# FPGA_Data.net
KiCad netlist of a schematic drawn in Altium Designer
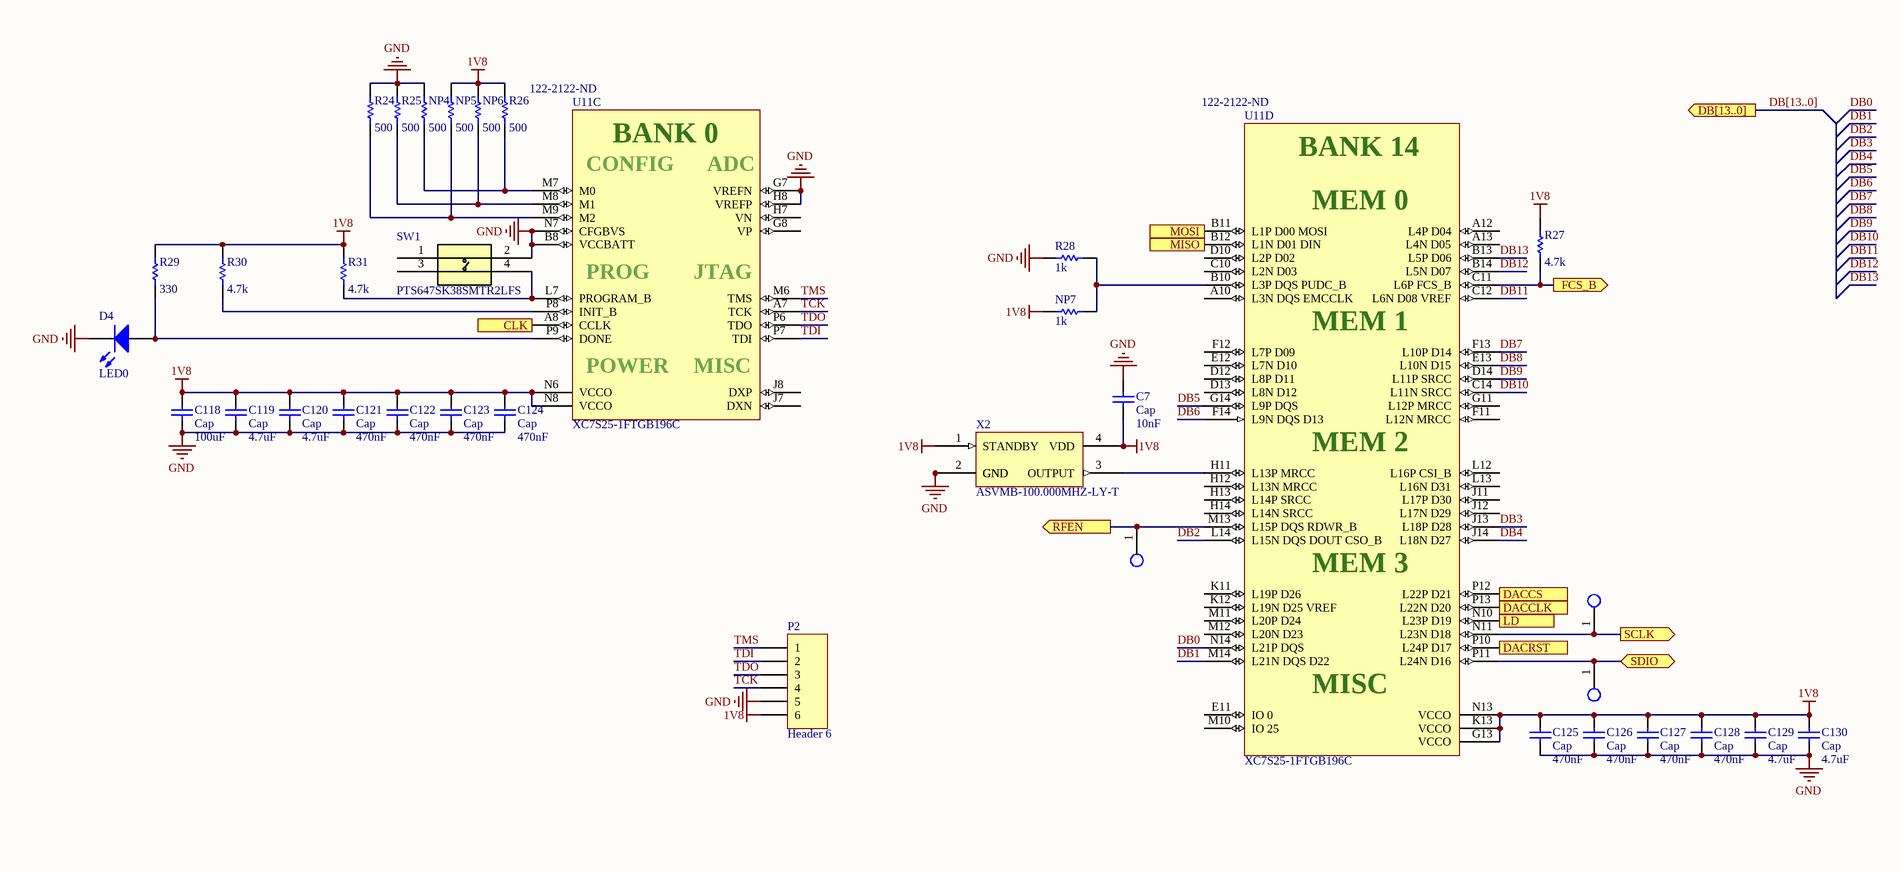
[diagram p0: FPGA Data.SchDoc, left]
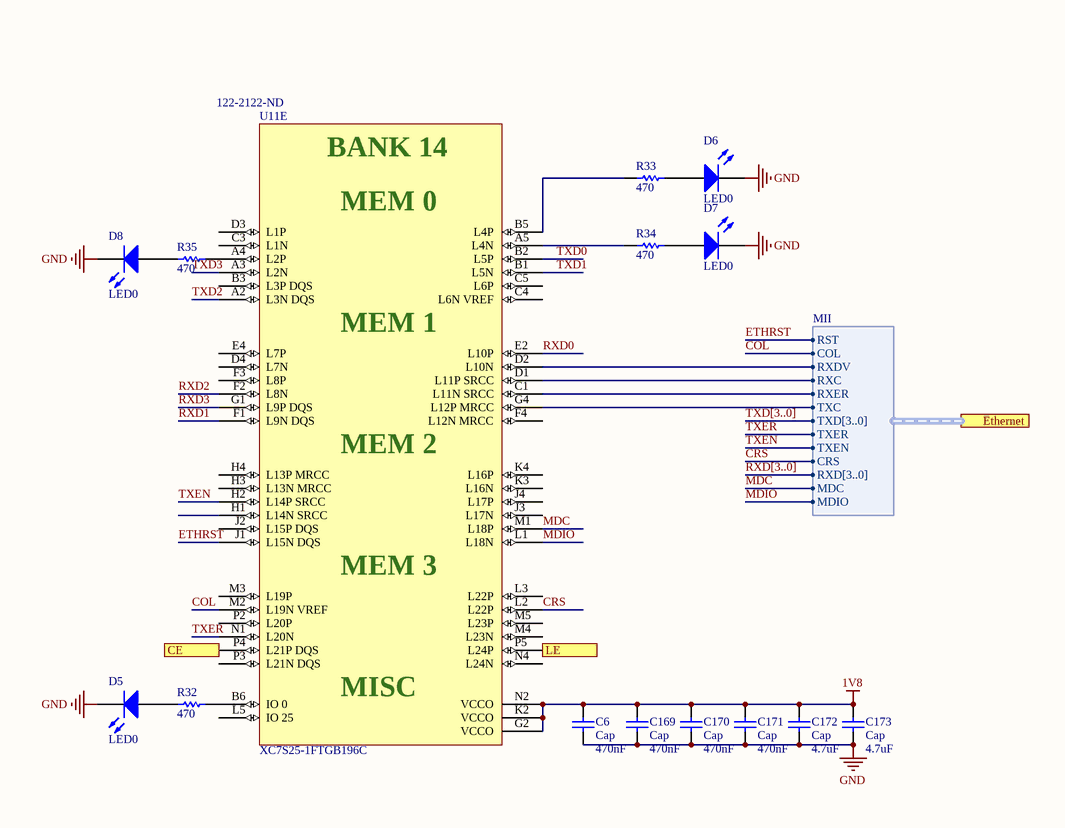
[diagram p1: FPGA Data.SchDoc, right]

(export (version "E")
  (design (tool "Eeschema 10.0.6"))
  (components
    (comp (ref "C6")
      (value "Cap")
      (footprint "1608[0603]")
      (description "Capacitor")
      (fields (field (name "ALTIUM_VALUE") "470nF") (field (name "PUBLISHER") "Altium Limited"))
      (libsource (lib "Miscellaneous Devices") (part "Cap"))
    )
    (comp (ref "C7")
      (value "Cap")
      (footprint "0402-A")
      (description "Capacitor")
      (fields (field (name "ALTIUM_VALUE") "10nF") (field (name "PUBLISHER") "Altium Limited"))
      (libsource (lib "Miscellaneous Devices") (part "Cap"))
    )
    (comp (ref "C118")
      (value "Cap")
      (footprint "C1210")
      (description "Capacitor")
      (fields (field (name "ALTIUM_VALUE") "100uF") (field (name "PUBLISHER") "Altium Limited"))
      (libsource (lib "Miscellaneous Devices") (part "Cap"))
    )
    (comp (ref "C119")
      (value "Cap")
      (footprint "6-0805_M")
      (description "Capacitor")
      (fields (field (name "ALTIUM_VALUE") "4.7uF") (field (name "PUBLISHER") "Altium Limited"))
      (libsource (lib "Miscellaneous Devices") (part "Cap"))
    )
    (comp (ref "C120")
      (value "Cap")
      (footprint "6-0805_M")
      (description "Capacitor")
      (fields (field (name "ALTIUM_VALUE") "4.7uF") (field (name "PUBLISHER") "Altium Limited"))
      (libsource (lib "Miscellaneous Devices") (part "Cap"))
    )
    (comp (ref "C121")
      (value "Cap")
      (footprint "1608[0603]")
      (description "Capacitor")
      (fields (field (name "ALTIUM_VALUE") "470nF") (field (name "PUBLISHER") "Altium Limited"))
      (libsource (lib "Miscellaneous Devices") (part "Cap"))
    )
    (comp (ref "C122")
      (value "Cap")
      (footprint "1608[0603]")
      (description "Capacitor")
      (fields (field (name "ALTIUM_VALUE") "470nF") (field (name "PUBLISHER") "Altium Limited"))
      (libsource (lib "Miscellaneous Devices") (part "Cap"))
    )
    (comp (ref "C123")
      (value "Cap")
      (footprint "1608[0603]")
      (description "Capacitor")
      (fields (field (name "ALTIUM_VALUE") "470nF") (field (name "PUBLISHER") "Altium Limited"))
      (libsource (lib "Miscellaneous Devices") (part "Cap"))
    )
    (comp (ref "C124")
      (value "Cap")
      (footprint "1608[0603]")
      (description "Capacitor")
      (fields (field (name "ALTIUM_VALUE") "470nF") (field (name "PUBLISHER") "Altium Limited"))
      (libsource (lib "Miscellaneous Devices") (part "Cap"))
    )
    (comp (ref "C125")
      (value "Cap")
      (footprint "1608[0603]")
      (description "Capacitor")
      (fields (field (name "ALTIUM_VALUE") "470nF") (field (name "PUBLISHER") "Altium Limited"))
      (libsource (lib "Miscellaneous Devices") (part "Cap"))
    )
    (comp (ref "C126")
      (value "Cap")
      (footprint "1608[0603]")
      (description "Capacitor")
      (fields (field (name "ALTIUM_VALUE") "470nF") (field (name "PUBLISHER") "Altium Limited"))
      (libsource (lib "Miscellaneous Devices") (part "Cap"))
    )
    (comp (ref "C127")
      (value "Cap")
      (footprint "1608[0603]")
      (description "Capacitor")
      (fields (field (name "ALTIUM_VALUE") "470nF") (field (name "PUBLISHER") "Altium Limited"))
      (libsource (lib "Miscellaneous Devices") (part "Cap"))
    )
    (comp (ref "C128")
      (value "Cap")
      (footprint "1608[0603]")
      (description "Capacitor")
      (fields (field (name "ALTIUM_VALUE") "470nF") (field (name "PUBLISHER") "Altium Limited"))
      (libsource (lib "Miscellaneous Devices") (part "Cap"))
    )
    (comp (ref "C129")
      (value "Cap")
      (footprint "6-0805_M")
      (description "Capacitor")
      (fields (field (name "ALTIUM_VALUE") "4.7uF") (field (name "PUBLISHER") "Altium Limited"))
      (libsource (lib "Miscellaneous Devices") (part "Cap"))
    )
    (comp (ref "C130")
      (value "Cap")
      (footprint "6-0805_M")
      (description "Capacitor")
      (fields (field (name "ALTIUM_VALUE") "4.7uF") (field (name "PUBLISHER") "Altium Limited"))
      (libsource (lib "Miscellaneous Devices") (part "Cap"))
    )
    (comp (ref "C169")
      (value "Cap")
      (footprint "1608[0603]")
      (description "Capacitor")
      (fields (field (name "ALTIUM_VALUE") "470nF") (field (name "PUBLISHER") "Altium Limited"))
      (libsource (lib "Miscellaneous Devices") (part "Cap"))
    )
    (comp (ref "C170")
      (value "Cap")
      (footprint "1608[0603]")
      (description "Capacitor")
      (fields (field (name "ALTIUM_VALUE") "470nF") (field (name "PUBLISHER") "Altium Limited"))
      (libsource (lib "Miscellaneous Devices") (part "Cap"))
    )
    (comp (ref "C171")
      (value "Cap")
      (footprint "1608[0603]")
      (description "Capacitor")
      (fields (field (name "ALTIUM_VALUE") "470nF") (field (name "PUBLISHER") "Altium Limited"))
      (libsource (lib "Miscellaneous Devices") (part "Cap"))
    )
    (comp (ref "C172")
      (value "Cap")
      (footprint "6-0805_M")
      (description "Capacitor")
      (fields (field (name "ALTIUM_VALUE") "4.7uF") (field (name "PUBLISHER") "Altium Limited"))
      (libsource (lib "Miscellaneous Devices") (part "Cap"))
    )
    (comp (ref "C173")
      (value "Cap")
      (footprint "6-0805_M")
      (description "Capacitor")
      (fields (field (name "ALTIUM_VALUE") "4.7uF") (field (name "PUBLISHER") "Altium Limited"))
      (libsource (lib "Miscellaneous Devices") (part "Cap"))
    )
    (comp (ref "CLK1")
      (value "5029")
      (footprint "EXPOSED PAD 0.02X0.02")
      (libsource (lib "5029") (part "5029"))
    )
    (comp (ref "CLK2")
      (value "5029")
      (footprint "EXPOSED PAD 0.02X0.02")
      (libsource (lib "5029") (part "5029"))
    )
    (comp (ref "CLK8")
      (value "5029")
      (footprint "EXPOSED PAD 0.02X0.02")
      (libsource (lib "5029") (part "5029"))
    )
    (comp (ref "D4")
      (value "LED0")
      (footprint "1608[0603]")
      (fields (field (name "PUBLISHER") "Altium Limited"))
      (libsource (lib "Miscellaneous Devices") (part "LED0"))
    )
    (comp (ref "D5")
      (value "LED0")
      (footprint "1608[0603]")
      (fields (field (name "PUBLISHER") "Altium Limited"))
      (libsource (lib "Miscellaneous Devices") (part "LED0"))
    )
    (comp (ref "D6")
      (value "LED0")
      (footprint "1608[0603]")
      (fields (field (name "PUBLISHER") "Altium Limited"))
      (libsource (lib "Miscellaneous Devices") (part "LED0"))
    )
    (comp (ref "D7")
      (value "LED0")
      (footprint "1608[0603]")
      (fields (field (name "PUBLISHER") "Altium Limited"))
      (libsource (lib "Miscellaneous Devices") (part "LED0"))
    )
    (comp (ref "D8")
      (value "LED0")
      (footprint "1608[0603]")
      (fields (field (name "PUBLISHER") "Altium Limited"))
      (libsource (lib "Miscellaneous Devices") (part "LED0"))
    )
    (comp (ref "NP4")
      (value "500")
      (footprint "0402-A")
      (description "Resistor")
      (fields (field (name "Comment") "Res1") (field (name "PUBLISHER") "Altium Limited"))
      (libsource (lib "Miscellaneous Devices") (part "Res1"))
    )
    (comp (ref "NP5")
      (value "500")
      (footprint "0402-A")
      (description "Resistor")
      (fields (field (name "Comment") "Res1") (field (name "PUBLISHER") "Altium Limited"))
      (libsource (lib "Miscellaneous Devices") (part "Res1"))
    )
    (comp (ref "NP6")
      (value "500")
      (footprint "0402-A")
      (description "Resistor")
      (fields (field (name "Comment") "Res1") (field (name "PUBLISHER") "Altium Limited"))
      (libsource (lib "Miscellaneous Devices") (part "Res1"))
    )
    (comp (ref "NP7")
      (value "1k")
      (footprint "0402-A")
      (description "Resistor")
      (fields (field (name "Comment") "Res1") (field (name "PUBLISHER") "Altium Limited"))
      (libsource (lib "Miscellaneous Devices") (part "Res1"))
    )
    (comp (ref "P2")
      (value "Header 6")
      (footprint "HDR1X6")
      (description "Header, 6-Pin")
      (fields (field (name "PUBLISHER") "Altium Limited"))
      (libsource (lib "Miscellaneous Connectors") (part "Header 6"))
    )
    (comp (ref "R24")
      (value "500")
      (footprint "0402-A")
      (description "Resistor")
      (fields (field (name "Comment") "Res1") (field (name "PUBLISHER") "Altium Limited"))
      (libsource (lib "Miscellaneous Devices") (part "Res1"))
    )
    (comp (ref "R25")
      (value "500")
      (footprint "0402-A")
      (description "Resistor")
      (fields (field (name "Comment") "Res1") (field (name "PUBLISHER") "Altium Limited"))
      (libsource (lib "Miscellaneous Devices") (part "Res1"))
    )
    (comp (ref "R26")
      (value "500")
      (footprint "0402-A")
      (description "Resistor")
      (fields (field (name "Comment") "Res1") (field (name "PUBLISHER") "Altium Limited"))
      (libsource (lib "Miscellaneous Devices") (part "Res1"))
    )
    (comp (ref "R27")
      (value "4.7k")
      (footprint "0402-A")
      (description "Resistor")
      (fields (field (name "Comment") "Res1") (field (name "PUBLISHER") "Altium Limited"))
      (libsource (lib "Miscellaneous Devices") (part "Res1"))
    )
    (comp (ref "R28")
      (value "1k")
      (footprint "0402-A")
      (description "Resistor")
      (fields (field (name "Comment") "Res1") (field (name "PUBLISHER") "Altium Limited"))
      (libsource (lib "Miscellaneous Devices") (part "Res1"))
    )
    (comp (ref "R29")
      (value "330")
      (footprint "0402-A")
      (description "Resistor")
      (fields (field (name "Comment") "Res1") (field (name "PUBLISHER") "Altium Limited"))
      (libsource (lib "Miscellaneous Devices") (part "Res1"))
    )
    (comp (ref "R30")
      (value "4.7k")
      (footprint "0402-A")
      (description "Resistor")
      (fields (field (name "Comment") "Res1") (field (name "PUBLISHER") "Altium Limited"))
      (libsource (lib "Miscellaneous Devices") (part "Res1"))
    )
    (comp (ref "R31")
      (value "4.7k")
      (footprint "0402-A")
      (description "Resistor")
      (fields (field (name "Comment") "Res1") (field (name "PUBLISHER") "Altium Limited"))
      (libsource (lib "Miscellaneous Devices") (part "Res1"))
    )
    (comp (ref "R32")
      (value "470")
      (footprint "0402-A")
      (description "Resistor")
      (fields (field (name "Comment") "Res1") (field (name "PUBLISHER") "Altium Limited"))
      (libsource (lib "Miscellaneous Devices") (part "Res1"))
    )
    (comp (ref "R33")
      (value "470")
      (footprint "0402-A")
      (description "Resistor")
      (fields (field (name "Comment") "Res1") (field (name "PUBLISHER") "Altium Limited"))
      (libsource (lib "Miscellaneous Devices") (part "Res1"))
    )
    (comp (ref "R34")
      (value "470")
      (footprint "0402-A")
      (description "Resistor")
      (fields (field (name "Comment") "Res1") (field (name "PUBLISHER") "Altium Limited"))
      (libsource (lib "Miscellaneous Devices") (part "Res1"))
    )
    (comp (ref "R35")
      (value "470")
      (footprint "0402-A")
      (description "Resistor")
      (fields (field (name "Comment") "Res1") (field (name "PUBLISHER") "Altium Limited"))
      (libsource (lib "Miscellaneous Devices") (part "Res1"))
    )
    (comp (ref "SW1")
      (value "PTS647SK38SMTR2LFS")
      (footprint "PTS647SK38SMTR2LFS_CNK")
      (description "No Description Available")
      (fields (field (name "COPYRIGHT") "Copyright (C) 2018 Accelerated Designs. All rights reserved"))
      (libsource (lib "PTS 647 SK38 SMTR2 LFS") (part "PTS647SK38SMTR2LFS"))
    )
    (comp (ref "U11")
      (value "XC7S25-1FTGB196C")
      (footprint "FTGB196 Package")
      (fields (field (name "SUPPLIER PART NUMBER 1") "122-2122-ND"))
      (libsource (lib "XC7S25-1FTGB196C") (part "XC7S25-1FTGB196C"))
    )
    (comp (ref "X2")
      (value "ASVMB-100.000MHZ-LY-T")
      (footprint "ASVMB-100.000MHZ-LY-T")
      (libsource (lib "ASVMB-100.000MHZ-LY-T") (part "ASVMB-100.000MHZ-LY-T"))
    )
  )
  (nets
    (net (code "2") (name "/CE") (class "Default")
      (node (ref "U11") (pin "P4") (pinfunction "L21P_DQS_P4") (pintype "bidirectional"))
    )
    (net (code "3") (name "/CLK") (class "Default")
      (node (ref "U11") (pin "A8") (pinfunction "CCLK_A8") (pintype "bidirectional"))
    )
    (net (code "4") (name "/COL") (class "Default")
      (node (ref "U11") (pin "M2") (pinfunction "L19N_VREF_M2") (pintype "bidirectional"))
    )
    (net (code "5") (name "/CRS") (class "Default")
      (node (ref "U11") (pin "L2") (pinfunction "L22P_L2") (pintype "bidirectional"))
    )
    (net (code "6") (name "/DACCLK") (class "Default")
      (node (ref "U11") (pin "P13") (pinfunction "L22N_D20_P13") (pintype "bidirectional"))
    )
    (net (code "7") (name "/DACCS") (class "Default")
      (node (ref "U11") (pin "P12") (pinfunction "L22P_D21_P12") (pintype "bidirectional"))
    )
    (net (code "8") (name "/DACRST") (class "Default")
      (node (ref "U11") (pin "P10") (pinfunction "L24P_D17_P10") (pintype "bidirectional"))
    )
    (net (code "9") (name "/DB0") (class "Default")
      (node (ref "U11") (pin "N14") (pinfunction "L21P_DQS_N14") (pintype "bidirectional"))
    )
    (net (code "10") (name "/DB1") (class "Default")
      (node (ref "U11") (pin "M14") (pinfunction "L21N_DQS_D22_M14") (pintype "bidirectional"))
    )
    (net (code "11") (name "/DB2") (class "Default")
      (node (ref "U11") (pin "L14") (pinfunction "L15N_DQS_DOUT_CSO_B_L14") (pintype "bidirectional"))
    )
    (net (code "12") (name "/DB3") (class "Default")
      (node (ref "U11") (pin "J13") (pinfunction "L18P_D28_J13") (pintype "bidirectional"))
    )
    (net (code "13") (name "/DB4") (class "Default")
      (node (ref "U11") (pin "J14") (pinfunction "L18N_D27_J14") (pintype "bidirectional"))
    )
    (net (code "14") (name "/DB5") (class "Default")
      (node (ref "U11") (pin "G14") (pinfunction "L9P_DQS_G14") (pintype "bidirectional"))
    )
    (net (code "15") (name "/DB6") (class "Default")
      (node (ref "U11") (pin "F14") (pinfunction "L9N_DQS_D13_F14") (pintype "input"))
    )
    (net (code "16") (name "/DB7") (class "Default")
      (node (ref "U11") (pin "F13") (pinfunction "L10P_D14_F13") (pintype "bidirectional"))
    )
    (net (code "17") (name "/DB8") (class "Default")
      (node (ref "U11") (pin "E13") (pinfunction "L10N_D15_E13") (pintype "bidirectional"))
    )
    (net (code "18") (name "/DB9") (class "Default")
      (node (ref "U11") (pin "D14") (pinfunction "L11P_SRCC_D14") (pintype "bidirectional"))
    )
    (net (code "19") (name "/DB10") (class "Default")
      (node (ref "U11") (pin "C14") (pinfunction "L11N_SRCC_C14") (pintype "bidirectional"))
    )
    (net (code "20") (name "/DB11") (class "Default")
      (node (ref "U11") (pin "C12") (pinfunction "L6N_D08_VREF_C12") (pintype "bidirectional"))
    )
    (net (code "21") (name "/DB12") (class "Default")
      (node (ref "U11") (pin "B14") (pinfunction "L5N_D07_B14") (pintype "bidirectional"))
    )
    (net (code "22") (name "/DB13") (class "Default")
      (node (ref "U11") (pin "B13") (pinfunction "L5P_D06_B13") (pintype "bidirectional"))
    )
    (net (code "24") (name "/ETHRST") (class "Default")
      (node (ref "U11") (pin "J1") (pinfunction "L15N_DQS_J1") (pintype "bidirectional"))
    )
    (net (code "26") (name "/FCS_B") (class "Default")
      (node (ref "R27") (pin "1") (pinfunction "1_1") (pintype "passive"))
      (node (ref "U11") (pin "C11") (pinfunction "L6P_FCS_B_C11") (pintype "bidirectional"))
    )
    (net (code "27") (name "/LD") (class "Default")
      (node (ref "U11") (pin "N10") (pinfunction "L23P_D19_N10") (pintype "bidirectional"))
    )
    (net (code "28") (name "/LE") (class "Default")
      (node (ref "U11") (pin "P5") (pinfunction "L24P_P5") (pintype "bidirectional"))
    )
    (net (code "29") (name "/MDC") (class "Default")
      (node (ref "U11") (pin "M1") (pinfunction "L18P_M1") (pintype "bidirectional"))
    )
    (net (code "30") (name "/MDIO") (class "Default")
      (node (ref "U11") (pin "L1") (pinfunction "L18N_L1") (pintype "bidirectional"))
    )
    (net (code "31") (name "/MISO") (class "Default")
      (node (ref "U11") (pin "B12") (pinfunction "L1N_D01_DIN_B12") (pintype "bidirectional"))
    )
    (net (code "32") (name "/MOSI") (class "Default")
      (node (ref "U11") (pin "B11") (pinfunction "L1P_D00_MOSI_B11") (pintype "bidirectional"))
    )
    (net (code "33") (name "/RFEN") (class "Default")
      (node (ref "CLK8") (pin "1") (pintype "passive"))
      (node (ref "U11") (pin "M13") (pinfunction "L15P_DQS_RDWR_B_M13") (pintype "bidirectional"))
    )
    (net (code "34") (name "/RXC") (class "Default")
      (node (ref "U11") (pin "D1") (pinfunction "L11P_SRCC_D1") (pintype "bidirectional"))
    )
    (net (code "35") (name "/RXD0") (class "Default")
      (node (ref "U11") (pin "E2") (pinfunction "L10P_E2") (pintype "bidirectional"))
    )
    (net (code "36") (name "/RXD1") (class "Default")
      (node (ref "U11") (pin "F1") (pinfunction "L9N_DQS_F1") (pintype "bidirectional"))
    )
    (net (code "37") (name "/RXD2") (class "Default")
      (node (ref "U11") (pin "F2") (pinfunction "L8N_F2") (pintype "bidirectional"))
    )
    (net (code "38") (name "/RXD3") (class "Default")
      (node (ref "U11") (pin "G1") (pinfunction "L9P_DQS_G1") (pintype "bidirectional"))
    )
    (net (code "39") (name "/RXDV") (class "Default")
      (node (ref "U11") (pin "D2") (pinfunction "L10N_D2") (pintype "bidirectional"))
    )
    (net (code "41") (name "/RXER") (class "Default")
      (node (ref "U11") (pin "C1") (pinfunction "L11N_SRCC_C1") (pintype "bidirectional"))
    )
    (net (code "42") (name "/SCLK") (class "Default")
      (node (ref "CLK1") (pin "1") (pintype "passive"))
      (node (ref "U11") (pin "N11") (pinfunction "L23N_D18_N11") (pintype "bidirectional"))
    )
    (net (code "43") (name "/SDIO") (class "Default")
      (node (ref "CLK2") (pin "1") (pintype "passive"))
      (node (ref "U11") (pin "P11") (pinfunction "L24N_D16_P11") (pintype "bidirectional"))
    )
    (net (code "44") (name "/TCK") (class "Default")
      (node (ref "P2") (pin "4") (pinfunction "4_4") (pintype "passive"))
      (node (ref "U11") (pin "A7") (pinfunction "TCK_A7") (pintype "bidirectional"))
    )
    (net (code "45") (name "/TDI") (class "Default")
      (node (ref "P2") (pin "2") (pinfunction "2_2") (pintype "passive"))
      (node (ref "U11") (pin "P7") (pinfunction "TDI_P7") (pintype "bidirectional"))
    )
    (net (code "46") (name "/TDO") (class "Default")
      (node (ref "P2") (pin "3") (pinfunction "3_3") (pintype "passive"))
      (node (ref "U11") (pin "P6") (pinfunction "TDO_P6") (pintype "bidirectional"))
    )
    (net (code "47") (name "/TMS") (class "Default")
      (node (ref "P2") (pin "1") (pinfunction "1_1") (pintype "passive"))
      (node (ref "U11") (pin "M6") (pinfunction "TMS_M6") (pintype "bidirectional"))
    )
    (net (code "48") (name "/TXC") (class "Default")
      (node (ref "U11") (pin "G4") (pinfunction "L12P_MRCC_G4") (pintype "bidirectional"))
    )
    (net (code "49") (name "/TXD0") (class "Default")
      (node (ref "U11") (pin "B2") (pinfunction "L5P_B2") (pintype "bidirectional"))
    )
    (net (code "50") (name "/TXD1") (class "Default")
      (node (ref "U11") (pin "B1") (pinfunction "L5N_B1") (pintype "bidirectional"))
    )
    (net (code "51") (name "/TXD2") (class "Default")
      (node (ref "U11") (pin "A2") (pinfunction "L3N_DQS_A2") (pintype "bidirectional"))
    )
    (net (code "52") (name "/TXD3") (class "Default")
      (node (ref "U11") (pin "A3") (pinfunction "L2N_A3") (pintype "bidirectional"))
    )
    (net (code "53") (name "/TXEN") (class "Default")
      (node (ref "U11") (pin "H2") (pinfunction "L14P_SRCC_H2") (pintype "bidirectional"))
    )
    (net (code "54") (name "/TXER") (class "Default")
      (node (ref "U11") (pin "N1") (pinfunction "L20N_N1") (pintype "bidirectional"))
    )
    (net (code "56") (name "1V8") (class "Default")
      (node (ref "C118") (pin "2") (pinfunction "2_2") (pintype "passive"))
      (node (ref "C119") (pin "2") (pinfunction "2_2") (pintype "passive"))
      (node (ref "C120") (pin "2") (pinfunction "2_2") (pintype "passive"))
      (node (ref "C121") (pin "2") (pinfunction "2_2") (pintype "passive"))
      (node (ref "C122") (pin "2") (pinfunction "2_2") (pintype "passive"))
      (node (ref "C123") (pin "2") (pinfunction "2_2") (pintype "passive"))
      (node (ref "C124") (pin "2") (pinfunction "2_2") (pintype "passive"))
      (node (ref "C125") (pin "2") (pinfunction "2_2") (pintype "passive"))
      (node (ref "C126") (pin "2") (pinfunction "2_2") (pintype "passive"))
      (node (ref "C127") (pin "2") (pinfunction "2_2") (pintype "passive"))
      (node (ref "C128") (pin "2") (pinfunction "2_2") (pintype "passive"))
      (node (ref "C129") (pin "2") (pinfunction "2_2") (pintype "passive"))
      (node (ref "C130") (pin "2") (pinfunction "2_2") (pintype "passive"))
      (node (ref "C169") (pin "2") (pinfunction "2_2") (pintype "passive"))
      (node (ref "C170") (pin "2") (pinfunction "2_2") (pintype "passive"))
      (node (ref "C171") (pin "2") (pinfunction "2_2") (pintype "passive"))
      (node (ref "C172") (pin "2") (pinfunction "2_2") (pintype "passive"))
      (node (ref "C173") (pin "2") (pinfunction "2_2") (pintype "passive"))
      (node (ref "C6") (pin "2") (pinfunction "2_2") (pintype "passive"))
      (node (ref "C7") (pin "1") (pinfunction "1_1") (pintype "passive"))
      (node (ref "NP5") (pin "2") (pinfunction "2_2") (pintype "passive"))
      (node (ref "NP6") (pin "2") (pinfunction "2_2") (pintype "passive"))
      (node (ref "NP7") (pin "2") (pinfunction "2_2") (pintype "passive"))
      (node (ref "P2") (pin "6") (pinfunction "6_6") (pintype "passive"))
      (node (ref "R26") (pin "2") (pinfunction "2_2") (pintype "passive"))
      (node (ref "R27") (pin "2") (pinfunction "2_2") (pintype "passive"))
      (node (ref "R29") (pin "2") (pinfunction "2_2") (pintype "passive"))
      (node (ref "R30") (pin "2") (pinfunction "2_2") (pintype "passive"))
      (node (ref "R31") (pin "2") (pinfunction "2_2") (pintype "passive"))
      (node (ref "U11") (pin "G13") (pinfunction "VCCO_G13") (pintype "power_in"))
      (node (ref "U11") (pin "G2") (pinfunction "VCCO_G2") (pintype "power_in"))
      (node (ref "U11") (pin "K13") (pinfunction "VCCO_K13") (pintype "power_in"))
      (node (ref "U11") (pin "K2") (pinfunction "VCCO_K2") (pintype "power_in"))
      (node (ref "U11") (pin "N13") (pinfunction "VCCO_N13") (pintype "power_in"))
      (node (ref "U11") (pin "N2") (pinfunction "VCCO_N2") (pintype "power_in"))
      (node (ref "U11") (pin "N6") (pinfunction "VCCO_N6") (pintype "power_in"))
      (node (ref "U11") (pin "N8") (pinfunction "VCCO_N8") (pintype "power_in"))
      (node (ref "X2") (pin "1") (pinfunction "STANDBY_1") (pintype "input"))
      (node (ref "X2") (pin "4") (pinfunction "VDD_4") (pintype "power_in"))
    )
    (net (code "57") (name "GND") (class "Default")
      (node (ref "C118") (pin "1") (pinfunction "1_1") (pintype "passive"))
      (node (ref "C119") (pin "1") (pinfunction "1_1") (pintype "passive"))
      (node (ref "C120") (pin "1") (pinfunction "1_1") (pintype "passive"))
      (node (ref "C121") (pin "1") (pinfunction "1_1") (pintype "passive"))
      (node (ref "C122") (pin "1") (pinfunction "1_1") (pintype "passive"))
      (node (ref "C123") (pin "1") (pinfunction "1_1") (pintype "passive"))
      (node (ref "C124") (pin "1") (pinfunction "1_1") (pintype "passive"))
      (node (ref "C125") (pin "1") (pinfunction "1_1") (pintype "passive"))
      (node (ref "C126") (pin "1") (pinfunction "1_1") (pintype "passive"))
      (node (ref "C127") (pin "1") (pinfunction "1_1") (pintype "passive"))
      (node (ref "C128") (pin "1") (pinfunction "1_1") (pintype "passive"))
      (node (ref "C129") (pin "1") (pinfunction "1_1") (pintype "passive"))
      (node (ref "C130") (pin "1") (pinfunction "1_1") (pintype "passive"))
      (node (ref "C169") (pin "1") (pinfunction "1_1") (pintype "passive"))
      (node (ref "C170") (pin "1") (pinfunction "1_1") (pintype "passive"))
      (node (ref "C171") (pin "1") (pinfunction "1_1") (pintype "passive"))
      (node (ref "C172") (pin "1") (pinfunction "1_1") (pintype "passive"))
      (node (ref "C173") (pin "1") (pinfunction "1_1") (pintype "passive"))
      (node (ref "C6") (pin "1") (pinfunction "1_1") (pintype "passive"))
      (node (ref "C7") (pin "2") (pinfunction "2_2") (pintype "passive"))
      (node (ref "D4") (pin "2") (pinfunction "K_2") (pintype "passive"))
      (node (ref "D5") (pin "2") (pinfunction "K_2") (pintype "passive"))
      (node (ref "D6") (pin "2") (pinfunction "K_2") (pintype "passive"))
      (node (ref "D7") (pin "2") (pinfunction "K_2") (pintype "passive"))
      (node (ref "D8") (pin "2") (pinfunction "K_2") (pintype "passive"))
      (node (ref "NP4") (pin "2") (pinfunction "2_2") (pintype "passive"))
      (node (ref "P2") (pin "5") (pinfunction "5_5") (pintype "passive"))
      (node (ref "R24") (pin "2") (pinfunction "2_2") (pintype "passive"))
      (node (ref "R25") (pin "2") (pinfunction "2_2") (pintype "passive"))
      (node (ref "R28") (pin "2") (pinfunction "2_2") (pintype "passive"))
      (node (ref "SW1") (pin "2") (pinfunction "2_2") (pintype "passive"))
      (node (ref "U11") (pin "B8") (pinfunction "VCCBATT_B8") (pintype "bidirectional"))
      (node (ref "U11") (pin "G7") (pinfunction "VREFN_G7") (pintype "bidirectional"))
      (node (ref "U11") (pin "H8") (pinfunction "VREFP_H8") (pintype "bidirectional"))
      (node (ref "U11") (pin "N7") (pinfunction "CFGBVS_N7") (pintype "bidirectional"))
      (node (ref "X2") (pin "2") (pinfunction "GND_2") (pintype "power_in"))
      (node (ref "X2") (pin "5") (pinfunction "GND_5") (pintype "power_in"))
    )
    (net (code "58") (name "Net-(D4-A)") (class "Default")
      (node (ref "D4") (pin "1") (pinfunction "A_1") (pintype "passive"))
      (node (ref "R29") (pin "1") (pinfunction "1_1") (pintype "passive"))
      (node (ref "U11") (pin "P9") (pinfunction "DONE_P9") (pintype "bidirectional"))
    )
    (net (code "59") (name "Net-(D5-A)") (class "Default")
      (node (ref "D5") (pin "1") (pinfunction "A_1") (pintype "passive"))
      (node (ref "R32") (pin "2") (pinfunction "2_2") (pintype "passive"))
    )
    (net (code "60") (name "Net-(D6-A)") (class "Default")
      (node (ref "D6") (pin "1") (pinfunction "A_1") (pintype "passive"))
      (node (ref "R33") (pin "2") (pinfunction "2_2") (pintype "passive"))
    )
    (net (code "61") (name "Net-(D7-A)") (class "Default")
      (node (ref "D7") (pin "1") (pinfunction "A_1") (pintype "passive"))
      (node (ref "R34") (pin "2") (pinfunction "2_2") (pintype "passive"))
    )
    (net (code "62") (name "Net-(D8-A)") (class "Default")
      (node (ref "D8") (pin "1") (pinfunction "A_1") (pintype "passive"))
      (node (ref "R35") (pin "2") (pinfunction "2_2") (pintype "passive"))
    )
    (net (code "63") (name "Net-(U11C-INIT_B)") (class "Default")
      (node (ref "R30") (pin "1") (pinfunction "1_1") (pintype "passive"))
      (node (ref "U11") (pin "P8") (pinfunction "INIT_B_P8") (pintype "bidirectional"))
    )
    (net (code "64") (name "Net-(U11C-M0)") (class "Default")
      (node (ref "NP4") (pin "1") (pinfunction "1_1") (pintype "passive"))
      (node (ref "R26") (pin "1") (pinfunction "1_1") (pintype "passive"))
      (node (ref "U11") (pin "M7") (pinfunction "M0_M7") (pintype "bidirectional"))
    )
    (net (code "65") (name "Net-(U11C-M1)") (class "Default")
      (node (ref "NP6") (pin "1") (pinfunction "1_1") (pintype "passive"))
      (node (ref "R25") (pin "1") (pinfunction "1_1") (pintype "passive"))
      (node (ref "U11") (pin "M8") (pinfunction "M1_M8") (pintype "bidirectional"))
    )
    (net (code "66") (name "Net-(U11C-M2)") (class "Default")
      (node (ref "NP5") (pin "1") (pinfunction "1_1") (pintype "passive"))
      (node (ref "R24") (pin "1") (pinfunction "1_1") (pintype "passive"))
      (node (ref "U11") (pin "M9") (pinfunction "M2_M9") (pintype "bidirectional"))
    )
    (net (code "67") (name "Net-(U11C-PROGRAM_B)") (class "Default")
      (node (ref "R31") (pin "1") (pinfunction "1_1") (pintype "passive"))
      (node (ref "SW1") (pin "4") (pinfunction "4_4") (pintype "passive"))
      (node (ref "U11") (pin "L7") (pinfunction "PROGRAM_B_L7") (pintype "bidirectional"))
    )
    (net (code "68") (name "Net-(U11D-L3P_DQS_PUDC_B)") (class "Default")
      (node (ref "NP7") (pin "1") (pinfunction "1_1") (pintype "passive"))
      (node (ref "R28") (pin "1") (pinfunction "1_1") (pintype "passive"))
      (node (ref "U11") (pin "B10") (pinfunction "L3P_DQS_PUDC_B_B10") (pintype "bidirectional"))
    )
    (net (code "69") (name "Net-(U11D-L13P_MRCC)") (class "Default")
      (node (ref "U11") (pin "H11") (pinfunction "L13P_MRCC_H11") (pintype "bidirectional"))
      (node (ref "X2") (pin "3") (pinfunction "OUTPUT_3") (pintype "output"))
    )
    (net (code "70") (name "Net-(U11E-IO_0)") (class "Default")
      (node (ref "R32") (pin "1") (pinfunction "1_1") (pintype "passive"))
      (node (ref "U11") (pin "B6") (pinfunction "IO_0_B6") (pintype "bidirectional"))
    )
    (net (code "71") (name "Net-(U11E-L2P)") (class "Default")
      (node (ref "R35") (pin "1") (pinfunction "1_1") (pintype "passive"))
      (node (ref "U11") (pin "A4") (pinfunction "L2P_A4") (pintype "bidirectional"))
    )
    (net (code "72") (name "Net-(U11E-L4N)") (class "Default")
      (node (ref "R34") (pin "1") (pinfunction "1_1") (pintype "passive"))
      (node (ref "U11") (pin "A5") (pinfunction "L4N_A5") (pintype "bidirectional"))
    )
    (net (code "73") (name "Net-(U11E-L4P)") (class "Default")
      (node (ref "R33") (pin "1") (pinfunction "1_1") (pintype "passive"))
      (node (ref "U11") (pin "B5") (pinfunction "L4P_B5") (pintype "bidirectional"))
    )
    (net (code "74") (name "unconnected-(SW1-Pad1)") (class "Default")
      (node (ref "SW1") (pin "1") (pinfunction "1_1") (pintype "passive"))
    )
    (net (code "75") (name "unconnected-(SW1-Pad3)") (class "Default")
      (node (ref "SW1") (pin "3") (pinfunction "3_3") (pintype "passive"))
    )
    (net (code "76") (name "unconnected-(U11C-DXN-PadJ7)") (class "Default")
      (node (ref "U11") (pin "J7") (pinfunction "DXN_J7") (pintype "bidirectional"))
    )
    (net (code "77") (name "unconnected-(U11C-DXP-PadJ8)") (class "Default")
      (node (ref "U11") (pin "J8") (pinfunction "DXP_J8") (pintype "bidirectional"))
    )
    (net (code "78") (name "unconnected-(U11C-VN-PadH7)") (class "Default")
      (node (ref "U11") (pin "H7") (pinfunction "VN_H7") (pintype "bidirectional"))
    )
    (net (code "79") (name "unconnected-(U11C-VP-PadG8)") (class "Default")
      (node (ref "U11") (pin "G8") (pinfunction "VP_G8") (pintype "bidirectional"))
    )
    (net (code "80") (name "unconnected-(U11D-IO_0-PadE11)") (class "Default")
      (node (ref "U11") (pin "E11") (pinfunction "IO_0_E11") (pintype "bidirectional"))
    )
    (net (code "81") (name "unconnected-(U11D-IO_25-PadM10)") (class "Default")
      (node (ref "U11") (pin "M10") (pinfunction "IO_25_M10") (pintype "bidirectional"))
    )
    (net (code "82") (name "unconnected-(U11D-L2N_D03-PadC10)") (class "Default")
      (node (ref "U11") (pin "C10") (pinfunction "L2N_D03_C10") (pintype "bidirectional"))
    )
    (net (code "83") (name "unconnected-(U11D-L2P_D02-PadD10)") (class "Default")
      (node (ref "U11") (pin "D10") (pinfunction "L2P_D02_D10") (pintype "bidirectional"))
    )
    (net (code "84") (name "unconnected-(U11D-L3N_DQS_EMCCLK-PadA10)") (class "Default")
      (node (ref "U11") (pin "A10") (pinfunction "L3N_DQS_EMCCLK_A10") (pintype "bidirectional"))
    )
    (net (code "85") (name "unconnected-(U11D-L4N_D05-PadA13)") (class "Default")
      (node (ref "U11") (pin "A13") (pinfunction "L4N_D05_A13") (pintype "bidirectional"))
    )
    (net (code "86") (name "unconnected-(U11D-L4P_D04-PadA12)") (class "Default")
      (node (ref "U11") (pin "A12") (pinfunction "L4P_D04_A12") (pintype "bidirectional"))
    )
    (net (code "87") (name "unconnected-(U11D-L7N_D10-PadE12)") (class "Default")
      (node (ref "U11") (pin "E12") (pinfunction "L7N_D10_E12") (pintype "bidirectional"))
    )
    (net (code "88") (name "unconnected-(U11D-L7P_D09-PadF12)") (class "Default")
      (node (ref "U11") (pin "F12") (pinfunction "L7P_D09_F12") (pintype "bidirectional"))
    )
    (net (code "89") (name "unconnected-(U11D-L8N_D12-PadD13)") (class "Default")
      (node (ref "U11") (pin "D13") (pinfunction "L8N_D12_D13") (pintype "bidirectional"))
    )
    (net (code "90") (name "unconnected-(U11D-L8P_D11-PadD12)") (class "Default")
      (node (ref "U11") (pin "D12") (pinfunction "L8P_D11_D12") (pintype "bidirectional"))
    )
    (net (code "91") (name "unconnected-(U11D-L12N_MRCC-PadF11)") (class "Default")
      (node (ref "U11") (pin "F11") (pinfunction "L12N_MRCC_F11") (pintype "bidirectional"))
    )
    (net (code "92") (name "unconnected-(U11D-L12P_MRCC-PadG11)") (class "Default")
      (node (ref "U11") (pin "G11") (pinfunction "L12P_MRCC_G11") (pintype "bidirectional"))
    )
    (net (code "93") (name "unconnected-(U11D-L13N_MRCC-PadH12)") (class "Default")
      (node (ref "U11") (pin "H12") (pinfunction "L13N_MRCC_H12") (pintype "bidirectional"))
    )
    (net (code "94") (name "unconnected-(U11D-L14N_SRCC-PadH14)") (class "Default")
      (node (ref "U11") (pin "H14") (pinfunction "L14N_SRCC_H14") (pintype "bidirectional"))
    )
    (net (code "95") (name "unconnected-(U11D-L14P_SRCC-PadH13)") (class "Default")
      (node (ref "U11") (pin "H13") (pinfunction "L14P_SRCC_H13") (pintype "bidirectional"))
    )
    (net (code "96") (name "unconnected-(U11D-L16N_D31-PadL13)") (class "Default")
      (node (ref "U11") (pin "L13") (pinfunction "L16N_D31_L13") (pintype "bidirectional"))
    )
    (net (code "97") (name "unconnected-(U11D-L16P_CSI_B-PadL12)") (class "Default")
      (node (ref "U11") (pin "L12") (pinfunction "L16P_CSI_B_L12") (pintype "bidirectional"))
    )
    (net (code "98") (name "unconnected-(U11D-L17N_D29-PadJ12)") (class "Default")
      (node (ref "U11") (pin "J12") (pinfunction "L17N_D29_J12") (pintype "bidirectional"))
    )
    (net (code "99") (name "unconnected-(U11D-L17P_D30-PadJ11)") (class "Default")
      (node (ref "U11") (pin "J11") (pinfunction "L17P_D30_J11") (pintype "bidirectional"))
    )
    (net (code "100") (name "unconnected-(U11D-L19N_D25_VREF-PadK12)") (class "Default")
      (node (ref "U11") (pin "K12") (pinfunction "L19N_D25_VREF_K12") (pintype "bidirectional"))
    )
    (net (code "101") (name "unconnected-(U11D-L19P_D26-PadK11)") (class "Default")
      (node (ref "U11") (pin "K11") (pinfunction "L19P_D26_K11") (pintype "bidirectional"))
    )
    (net (code "102") (name "unconnected-(U11D-L20N_D23-PadM12)") (class "Default")
      (node (ref "U11") (pin "M12") (pinfunction "L20N_D23_M12") (pintype "bidirectional"))
    )
    (net (code "103") (name "unconnected-(U11D-L20P_D24-PadM11)") (class "Default")
      (node (ref "U11") (pin "M11") (pinfunction "L20P_D24_M11") (pintype "bidirectional"))
    )
    (net (code "104") (name "unconnected-(U11E-IO_25-PadL5)") (class "Default")
      (node (ref "U11") (pin "L5") (pinfunction "IO_25_L5") (pintype "bidirectional"))
    )
    (net (code "105") (name "unconnected-(U11E-L1N-PadC3)") (class "Default")
      (node (ref "U11") (pin "C3") (pinfunction "L1N_C3") (pintype "bidirectional"))
    )
    (net (code "106") (name "unconnected-(U11E-L1P-PadD3)") (class "Default")
      (node (ref "U11") (pin "D3") (pinfunction "L1P_D3") (pintype "bidirectional"))
    )
    (net (code "107") (name "unconnected-(U11E-L3P_DQS-PadB3)") (class "Default")
      (node (ref "U11") (pin "B3") (pinfunction "L3P_DQS_B3") (pintype "bidirectional"))
    )
    (net (code "108") (name "unconnected-(U11E-L6N_VREF-PadC4)") (class "Default")
      (node (ref "U11") (pin "C4") (pinfunction "L6N_VREF_C4") (pintype "bidirectional"))
    )
    (net (code "109") (name "unconnected-(U11E-L6P-PadC5)") (class "Default")
      (node (ref "U11") (pin "C5") (pinfunction "L6P_C5") (pintype "bidirectional"))
    )
    (net (code "110") (name "unconnected-(U11E-L7N-PadD4)") (class "Default")
      (node (ref "U11") (pin "D4") (pinfunction "L7N_D4") (pintype "bidirectional"))
    )
    (net (code "111") (name "unconnected-(U11E-L7P-PadE4)") (class "Default")
      (node (ref "U11") (pin "E4") (pinfunction "L7P_E4") (pintype "bidirectional"))
    )
    (net (code "112") (name "unconnected-(U11E-L8P-PadF3)") (class "Default")
      (node (ref "U11") (pin "F3") (pinfunction "L8P_F3") (pintype "bidirectional"))
    )
    (net (code "113") (name "unconnected-(U11E-L12N_MRCC-PadF4)") (class "Default")
      (node (ref "U11") (pin "F4") (pinfunction "L12N_MRCC_F4") (pintype "bidirectional"))
    )
    (net (code "114") (name "unconnected-(U11E-L13N_MRCC-PadH3)") (class "Default")
      (node (ref "U11") (pin "H3") (pinfunction "L13N_MRCC_H3") (pintype "bidirectional"))
    )
    (net (code "115") (name "unconnected-(U11E-L13P_MRCC-PadH4)") (class "Default")
      (node (ref "U11") (pin "H4") (pinfunction "L13P_MRCC_H4") (pintype "bidirectional"))
    )
    (net (code "116") (name "unconnected-(U11E-L14N_SRCC-PadH1)") (class "Default")
      (node (ref "U11") (pin "H1") (pinfunction "L14N_SRCC_H1") (pintype "bidirectional"))
    )
    (net (code "117") (name "unconnected-(U11E-L15P_DQS-PadJ2)") (class "Default")
      (node (ref "U11") (pin "J2") (pinfunction "L15P_DQS_J2") (pintype "bidirectional"))
    )
    (net (code "118") (name "unconnected-(U11E-L16N-PadK3)") (class "Default")
      (node (ref "U11") (pin "K3") (pinfunction "L16N_K3") (pintype "bidirectional"))
    )
    (net (code "119") (name "unconnected-(U11E-L16P-PadK4)") (class "Default")
      (node (ref "U11") (pin "K4") (pinfunction "L16P_K4") (pintype "bidirectional"))
    )
    (net (code "120") (name "unconnected-(U11E-L17N-PadJ3)") (class "Default")
      (node (ref "U11") (pin "J3") (pinfunction "L17N_J3") (pintype "bidirectional"))
    )
    (net (code "121") (name "unconnected-(U11E-L17P-PadJ4)") (class "Default")
      (node (ref "U11") (pin "J4") (pinfunction "L17P_J4") (pintype "bidirectional"))
    )
    (net (code "122") (name "unconnected-(U11E-L19P-PadM3)") (class "Default")
      (node (ref "U11") (pin "M3") (pinfunction "L19P_M3") (pintype "bidirectional"))
    )
    (net (code "123") (name "unconnected-(U11E-L20P-PadP2)") (class "Default")
      (node (ref "U11") (pin "P2") (pinfunction "L20P_P2") (pintype "bidirectional"))
    )
    (net (code "124") (name "unconnected-(U11E-L21N_DQS-PadP3)") (class "Default")
      (node (ref "U11") (pin "P3") (pinfunction "L21N_DQS_P3") (pintype "bidirectional"))
    )
    (net (code "125") (name "unconnected-(U11E-L22P-PadL3)") (class "Default")
      (node (ref "U11") (pin "L3") (pinfunction "L22P_L3") (pintype "bidirectional"))
    )
    (net (code "126") (name "unconnected-(U11E-L23N-PadM4)") (class "Default")
      (node (ref "U11") (pin "M4") (pinfunction "L23N_M4") (pintype "bidirectional"))
    )
    (net (code "127") (name "unconnected-(U11E-L23P-PadM5)") (class "Default")
      (node (ref "U11") (pin "M5") (pinfunction "L23P_M5") (pintype "bidirectional"))
    )
    (net (code "128") (name "unconnected-(U11E-L24N-PadN4)") (class "Default")
      (node (ref "U11") (pin "N4") (pinfunction "L24N_N4") (pintype "bidirectional"))
    )
  )
)
